# H-Bridge.net
KiCad netlist of a schematic drawn in Altium Designer
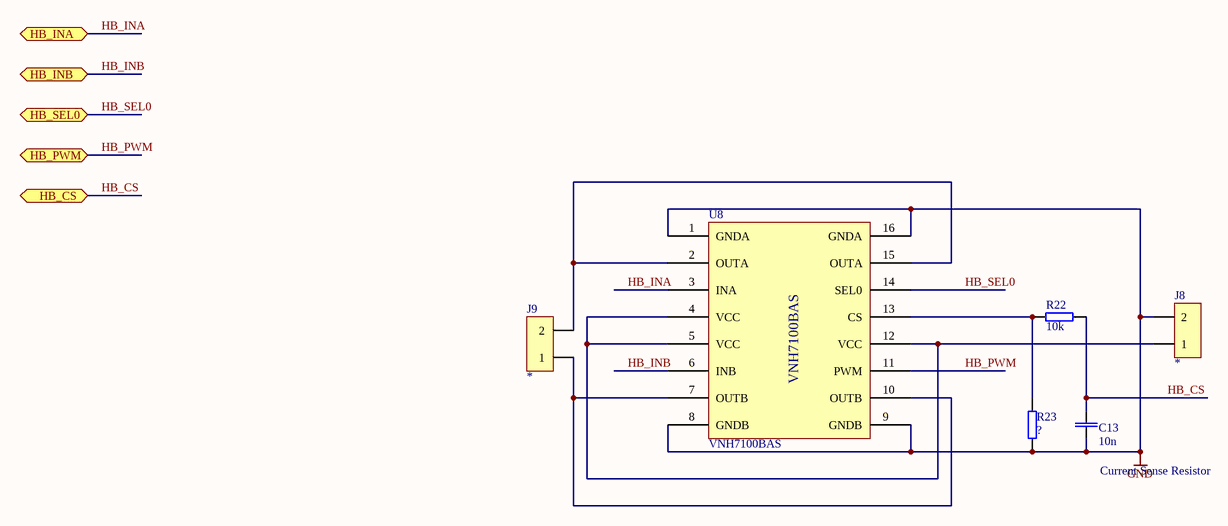
[diagram p0: H-Bridge.SchDoc]

(export (version "E")
  (design (tool "Eeschema 10.0.6"))
  (components
    (comp (ref "C13")
      (value "10n")
      (footprint "CAP 0805")
      (description "NON POLARIZED CAPACITOR")
      (libsource (lib "SCH_LIB") (part "CAP"))
    )
    (comp (ref "J8")
      (value "*")
      (footprint "PTR_AKZ350")
      (description "2 PIN HEADER")
      (libsource (lib "SCH_LIB") (part "HEADER2"))
    )
    (comp (ref "J9")
      (value "*")
      (footprint "PTR_AKZ350")
      (description "2 PIN HEADER")
      (libsource (lib "") (part "HEADER2_1"))
    )
    (comp (ref "R22")
      (value "10k")
      (footprint "RES 0805")
      (description "RESISTOR")
      (libsource (lib "") (part "RES_1"))
    )
    (comp (ref "R23")
      (value "?")
      (footprint "RES 0805")
      (description "RESISTOR")
      (libsource (lib "SCH_LIB") (part "RES"))
    )
    (comp (ref "U8")
      (value "VNH7100BAS")
      (footprint "SO16N")
      (description "Automotive fully integrated H-bridge motor driver")
      (libsource (lib "SCH_LIB") (part "VNH7100BAS"))
    )
  )
  (nets
    (net (code "1") (name "/HB_CS") (class "Default")
      (node (ref "C13") (pin "2") (pinfunction "2_2") (pintype "passive"))
      (node (ref "R22") (pin "2") (pinfunction "2_2") (pintype "passive"))
    )
    (net (code "2") (name "/HB_INA") (class "Default")
      (node (ref "U8") (pin "3") (pinfunction "INA_3") (pintype "passive"))
    )
    (net (code "3") (name "/HB_INB") (class "Default")
      (node (ref "U8") (pin "6") (pinfunction "INB_6") (pintype "passive"))
    )
    (net (code "4") (name "/HB_PWM") (class "Default")
      (node (ref "U8") (pin "11") (pinfunction "PWM_11") (pintype "passive"))
    )
    (net (code "5") (name "/HB_SEL0") (class "Default")
      (node (ref "U8") (pin "14") (pinfunction "SEL0_14") (pintype "passive"))
    )
    (net (code "6") (name "GND") (class "Default")
      (node (ref "C13") (pin "1") (pinfunction "1_1") (pintype "passive"))
      (node (ref "J8") (pin "2") (pinfunction "2_2") (pintype "passive"))
      (node (ref "R23") (pin "2") (pinfunction "2_2") (pintype "passive"))
      (node (ref "U8") (pin "1") (pinfunction "GNDA_1") (pintype "passive"))
      (node (ref "U8") (pin "16") (pinfunction "GNDA_16") (pintype "passive"))
      (node (ref "U8") (pin "8") (pinfunction "GNDB_8") (pintype "passive"))
      (node (ref "U8") (pin "9") (pinfunction "GNDB_9") (pintype "passive"))
    )
    (net (code "7") (name "Net-(J8-Pad1)") (class "Default")
      (node (ref "J8") (pin "1") (pinfunction "1_1") (pintype "passive"))
      (node (ref "U8") (pin "12") (pinfunction "VCC_12") (pintype "passive"))
      (node (ref "U8") (pin "4") (pinfunction "VCC_4") (pintype "passive"))
      (node (ref "U8") (pin "5") (pinfunction "VCC_5") (pintype "passive"))
    )
    (net (code "8") (name "Net-(J9-Pad1)") (class "Default")
      (node (ref "J9") (pin "1") (pinfunction "1_1") (pintype "passive"))
      (node (ref "U8") (pin "10") (pinfunction "OUTB_10") (pintype "passive"))
      (node (ref "U8") (pin "7") (pinfunction "OUTB_7") (pintype "passive"))
    )
    (net (code "9") (name "Net-(J9-Pad2)") (class "Default")
      (node (ref "J9") (pin "2") (pinfunction "2_2") (pintype "passive"))
      (node (ref "U8") (pin "15") (pinfunction "OUTA_15") (pintype "passive"))
      (node (ref "U8") (pin "2") (pinfunction "OUTA_2") (pintype "passive"))
    )
    (net (code "10") (name "Net-(U8-CS)") (class "Default")
      (node (ref "R22") (pin "1") (pinfunction "1_1") (pintype "passive"))
      (node (ref "R23") (pin "1") (pinfunction "1_1") (pintype "passive"))
      (node (ref "U8") (pin "13") (pinfunction "CS_13") (pintype "passive"))
    )
  )
)
